# pic24rgbdin-01.net
KiCad netlist of a schematic drawn in EAGLE
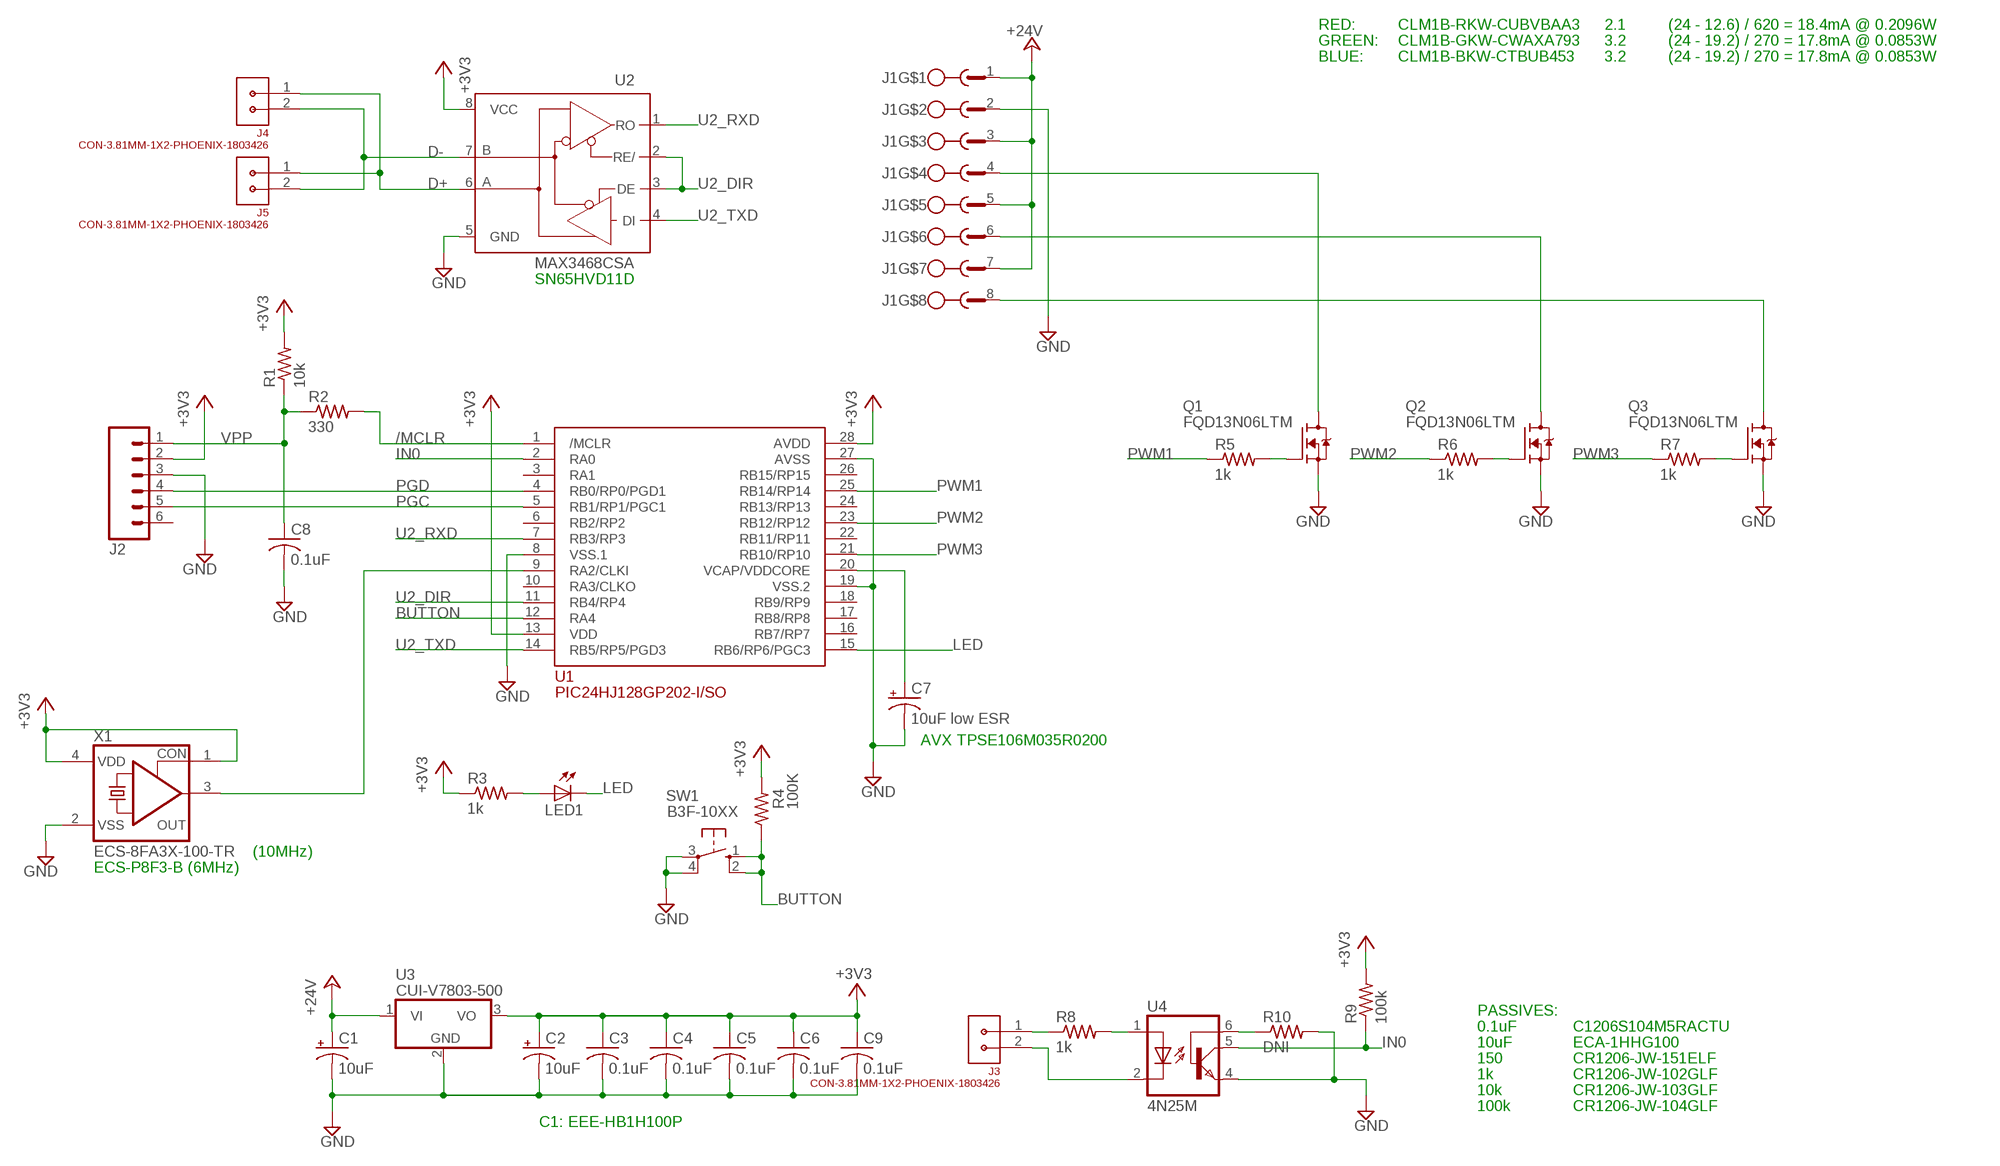
[diagram p0: schematic, sheet 1]

(export (version "E")
  (design (tool "Eeschema 10.0.6"))
  (components
    (comp (ref "C1")
      (value "10uF")
      (footprint "eagle-import:PANASONIC_D")
      (libsource (lib "eagle-import") (part "CPOL-USD"))
    )
    (comp (ref "C2")
      (value "10uF")
      (footprint "eagle-import:PANASONIC_D")
      (libsource (lib "eagle-import") (part "CPOL-USD"))
    )
    (comp (ref "C3")
      (value "0.1uF")
      (footprint "eagle-import:C1206")
      (libsource (lib "eagle-import") (part "C-USC1206"))
    )
    (comp (ref "C4")
      (value "0.1uF")
      (footprint "eagle-import:C1206")
      (libsource (lib "eagle-import") (part "C-USC1206"))
    )
    (comp (ref "C5")
      (value "0.1uF")
      (footprint "eagle-import:C1206")
      (libsource (lib "eagle-import") (part "C-USC1206"))
    )
    (comp (ref "C6")
      (value "0.1uF")
      (footprint "eagle-import:C1206")
      (libsource (lib "eagle-import") (part "C-USC1206"))
    )
    (comp (ref "C7")
      (value "10uF low ESR")
      (footprint "eagle-import:D_7343-31R")
      (libsource (lib "eagle-import") (part "CPOL-USD/7343-31R"))
    )
    (comp (ref "C8")
      (value "0.1uF")
      (footprint "eagle-import:C1206")
      (libsource (lib "eagle-import") (part "C-USC1206"))
    )
    (comp (ref "C9")
      (value "0.1uF")
      (footprint "eagle-import:C1206")
      (libsource (lib "eagle-import") (part "C-USC1206"))
    )
    (comp (ref "J1")
      (value "CON-3.81MM-1X8-PHOENIX-HEADER-1803484")
      (footprint "eagle-import:CON-PHOENIX-1803484-3.81-1X8")
      (libsource (lib "eagle-import") (part "CON-3.81MM-1X8-PHOENIX-HEADER-1803484"))
    )
    (comp (ref "J2")
      (value "M06SIP")
      (footprint "eagle-import:1X06")
      (libsource (lib "eagle-import") (part "M06SIP"))
    )
    (comp (ref "J3")
      (value "CON-3.81MM-1X2-PHOENIX-1803426")
      (footprint "eagle-import:CON-PHOENIX-1803426-3.81-1X2")
      (libsource (lib "eagle-import") (part "CON-3.81MM-1X2-PHOENIX-1803426"))
    )
    (comp (ref "J4")
      (value "CON-3.81MM-1X2-PHOENIX-1803426")
      (footprint "eagle-import:CON-PHOENIX-1803426-3.81-1X2")
      (libsource (lib "eagle-import") (part "CON-3.81MM-1X2-PHOENIX-1803426"))
    )
    (comp (ref "J5")
      (value "CON-3.81MM-1X2-PHOENIX-1803426")
      (footprint "eagle-import:CON-PHOENIX-1803426-3.81-1X2")
      (libsource (lib "eagle-import") (part "CON-3.81MM-1X2-PHOENIX-1803426"))
    )
    (comp (ref "LED1")
      (value "LED3MM")
      (footprint "eagle-import:LED3MM")
      (libsource (lib "eagle-import") (part "LED3MM"))
    )
    (comp (ref "Q1")
      (value "FQD13N06LTM")
      (footprint "eagle-import:TO252-D-PAK-FQD13N06LTM")
      (libsource (lib "eagle-import") (part "FQD13N06L"))
    )
    (comp (ref "Q2")
      (value "FQD13N06LTM")
      (footprint "eagle-import:TO252-D-PAK-FQD13N06LTM")
      (libsource (lib "eagle-import") (part "FQD13N06L"))
    )
    (comp (ref "Q3")
      (value "FQD13N06LTM")
      (footprint "eagle-import:TO252-D-PAK-FQD13N06LTM")
      (libsource (lib "eagle-import") (part "FQD13N06L"))
    )
    (comp (ref "R1")
      (value "10k")
      (footprint "eagle-import:R1206")
      (libsource (lib "eagle-import") (part "R-US_R1206"))
    )
    (comp (ref "R2")
      (value "330")
      (footprint "eagle-import:R1206")
      (libsource (lib "eagle-import") (part "R-US_R1206"))
    )
    (comp (ref "R3")
      (value "1k")
      (footprint "eagle-import:R1206")
      (libsource (lib "eagle-import") (part "R-US_R1206"))
    )
    (comp (ref "R4")
      (value "100K")
      (footprint "eagle-import:M1206")
      (libsource (lib "eagle-import") (part "R-US_M1206"))
    )
    (comp (ref "R5")
      (value "1k")
      (footprint "eagle-import:R1206")
      (libsource (lib "eagle-import") (part "R-US_R1206"))
    )
    (comp (ref "R6")
      (value "1k")
      (footprint "eagle-import:R1206")
      (libsource (lib "eagle-import") (part "R-US_R1206"))
    )
    (comp (ref "R7")
      (value "1k")
      (footprint "eagle-import:R1206")
      (libsource (lib "eagle-import") (part "R-US_R1206"))
    )
    (comp (ref "R8")
      (value "1k")
      (footprint "eagle-import:R1206")
      (libsource (lib "eagle-import") (part "R-US_R1206"))
    )
    (comp (ref "R9")
      (value "100k")
      (footprint "eagle-import:R1206")
      (libsource (lib "eagle-import") (part "R-US_R1206"))
    )
    (comp (ref "R10")
      (value "DNI")
      (footprint "eagle-import:R1206")
      (libsource (lib "eagle-import") (part "R-US_R1206"))
    )
    (comp (ref "SW1")
      (value "B3F-10XX")
      (footprint "eagle-import:B3F-10XX")
      (libsource (lib "eagle-import") (part "10-XX"))
    )
    (comp (ref "U1")
      (value "PIC24HJ128GP202-I/SO")
      (footprint "eagle-import:SO28W")
      (libsource (lib "eagle-import") (part "PIC24HJ128GP202-I/SO"))
    )
    (comp (ref "U2")
      (value "MAX3468CSA")
      (footprint "eagle-import:SO08")
      (fields (field (name "MPN") "MAX3468CSA+"))
      (libsource (lib "eagle-import") (part "MAX34SA68C"))
    )
    (comp (ref "U3")
      (value "CUI-V7803-500")
      (footprint "eagle-import:CUI-78XX-500")
      (libsource (lib "eagle-import") (part "CUI-V7803-500"))
    )
    (comp (ref "U4")
      (value "4N25M")
      (footprint "eagle-import:DIL06")
      (fields (field (name "MPN") "4N25-M"))
      (libsource (lib "eagle-import") (part "4N?M25"))
    )
    (comp (ref "X1")
      (value "ECS-8FA3X-100-TR")
      (footprint "eagle-import:1100S")
      (libsource (lib "eagle-import") (part "CRYSTAL_RES-1100S"))
    )
  )
  (nets
    (net (code "1") (name "+3V3") (class "Default")
      (node (ref "C2") (pin "+") (pinfunction "+_+") (pintype "passive"))
      (node (ref "C3") (pin "1") (pinfunction "1_1") (pintype "passive"))
      (node (ref "C4") (pin "1") (pinfunction "1_1") (pintype "passive"))
      (node (ref "C5") (pin "1") (pinfunction "1_1") (pintype "passive"))
      (node (ref "C6") (pin "1") (pinfunction "1_1") (pintype "passive"))
      (node (ref "C9") (pin "1") (pinfunction "1_1") (pintype "passive"))
      (node (ref "J2") (pin "2") (pinfunction "2_2") (pintype "passive"))
      (node (ref "R1") (pin "2") (pinfunction "2_2") (pintype "passive"))
      (node (ref "R3") (pin "1") (pinfunction "1_1") (pintype "passive"))
      (node (ref "R4") (pin "2") (pinfunction "2_2") (pintype "passive"))
      (node (ref "R9") (pin "2") (pinfunction "2_2") (pintype "passive"))
      (node (ref "U1") (pin "13") (pinfunction "VDD_13") (pintype "bidirectional"))
      (node (ref "U1") (pin "28") (pinfunction "AVDD_28") (pintype "bidirectional"))
      (node (ref "U2") (pin "8") (pinfunction "VCC_8") (pintype "power_in"))
      (node (ref "U3") (pin "3") (pinfunction "VO_3") (pintype "passive"))
      (node (ref "X1") (pin "1") (pinfunction "CON_1") (pintype "input"))
      (node (ref "X1") (pin "4") (pinfunction "VDD_4") (pintype "power_in"))
    )
    (net (code "2") (name "+24V") (class "Default")
      (node (ref "C1") (pin "+") (pinfunction "+_+") (pintype "passive"))
      (node (ref "J1") (pin "1") (pinfunction "1_1") (pintype "passive"))
      (node (ref "J1") (pin "3") (pinfunction "1_3") (pintype "passive"))
      (node (ref "J1") (pin "5") (pinfunction "1_5") (pintype "passive"))
      (node (ref "J1") (pin "7") (pinfunction "1_7") (pintype "passive"))
      (node (ref "U3") (pin "1") (pinfunction "VI_1") (pintype "input"))
    )
    (net (code "3") (name "/BUTTON") (class "Default")
      (node (ref "R4") (pin "1") (pinfunction "1_1") (pintype "passive"))
      (node (ref "SW1") (pin "1") (pinfunction "S_1") (pintype "passive"))
      (node (ref "SW1") (pin "2") (pinfunction "S1_2") (pintype "passive"))
      (node (ref "U1") (pin "12") (pinfunction "RA4_12") (pintype "bidirectional"))
    )
    (net (code "4") (name "/D+") (class "Default")
      (node (ref "J4") (pin "1") (pinfunction "1_1") (pintype "bidirectional"))
      (node (ref "J5") (pin "1") (pinfunction "1_1") (pintype "bidirectional"))
      (node (ref "U2") (pin "6") (pinfunction "A_6") (pintype "passive"))
    )
    (net (code "5") (name "/D-") (class "Default")
      (node (ref "J4") (pin "2") (pinfunction "2_2") (pintype "bidirectional"))
      (node (ref "J5") (pin "2") (pinfunction "2_2") (pintype "bidirectional"))
      (node (ref "U2") (pin "7") (pinfunction "B_7") (pintype "passive"))
    )
    (net (code "6") (name "/IN0") (class "Default")
      (node (ref "R9") (pin "1") (pinfunction "1_1") (pintype "passive"))
      (node (ref "U1") (pin "2") (pinfunction "RA0_2") (pintype "bidirectional"))
      (node (ref "U4") (pin "5") (pinfunction "COL_5") (pintype "passive"))
    )
    (net (code "7") (name "/LED") (class "Default")
      (node (ref "LED1") (pin "K") (pinfunction "C_K") (pintype "passive"))
      (node (ref "U1") (pin "15") (pinfunction "RB6/RP6/PGC3_15") (pintype "bidirectional"))
    )
    (net (code "8") (name "/PGC") (class "Default")
      (node (ref "J2") (pin "5") (pinfunction "5_5") (pintype "passive"))
      (node (ref "U1") (pin "5") (pinfunction "RB1/RP1/PGC1_5") (pintype "bidirectional"))
    )
    (net (code "9") (name "/PGD") (class "Default")
      (node (ref "J2") (pin "4") (pinfunction "4_4") (pintype "passive"))
      (node (ref "U1") (pin "4") (pinfunction "RB0/RP0/PGD1_4") (pintype "bidirectional"))
    )
    (net (code "10") (name "/PWM1") (class "Default")
      (node (ref "R5") (pin "1") (pinfunction "1_1") (pintype "passive"))
      (node (ref "U1") (pin "25") (pinfunction "RB14/RP14_25") (pintype "bidirectional"))
    )
    (net (code "11") (name "/PWM2") (class "Default")
      (node (ref "R6") (pin "1") (pinfunction "1_1") (pintype "passive"))
      (node (ref "U1") (pin "23") (pinfunction "RB12/RP12_23") (pintype "bidirectional"))
    )
    (net (code "12") (name "/PWM3") (class "Default")
      (node (ref "R7") (pin "1") (pinfunction "1_1") (pintype "passive"))
      (node (ref "U1") (pin "21") (pinfunction "RB10/RP10_21") (pintype "bidirectional"))
    )
    (net (code "13") (name "/U2_DIR") (class "Default")
      (node (ref "U1") (pin "11") (pinfunction "RB4/RP4_11") (pintype "bidirectional"))
      (node (ref "U2") (pin "2") (pinfunction "RE/_2") (pintype "input"))
      (node (ref "U2") (pin "3") (pinfunction "DE_3") (pintype "input"))
    )
    (net (code "14") (name "/U2_RXD") (class "Default")
      (node (ref "U1") (pin "7") (pinfunction "RB3/RP3_7") (pintype "bidirectional"))
      (node (ref "U2") (pin "1") (pinfunction "RO_1") (pintype "output"))
    )
    (net (code "15") (name "/U2_TXD") (class "Default")
      (node (ref "U1") (pin "14") (pinfunction "RB5/RP5/PGD3_14") (pintype "bidirectional"))
      (node (ref "U2") (pin "4") (pinfunction "DI_4") (pintype "input"))
    )
    (net (code "16") (name "/VPP") (class "Default")
      (node (ref "C8") (pin "1") (pinfunction "1_1") (pintype "passive"))
      (node (ref "J2") (pin "1") (pinfunction "1_1") (pintype "passive"))
      (node (ref "R1") (pin "1") (pinfunction "1_1") (pintype "passive"))
      (node (ref "R2") (pin "1") (pinfunction "1_1") (pintype "passive"))
    )
    (net (code "17") (name "/{slash}MCLR") (class "Default")
      (node (ref "R2") (pin "2") (pinfunction "2_2") (pintype "passive"))
      (node (ref "U1") (pin "1") (pinfunction "/MCLR_1") (pintype "bidirectional"))
    )
    (net (code "18") (name "GND") (class "Default")
      (node (ref "C1") (pin "-") (pinfunction "-_-") (pintype "passive"))
      (node (ref "C2") (pin "-") (pinfunction "-_-") (pintype "passive"))
      (node (ref "C3") (pin "2") (pinfunction "2_2") (pintype "passive"))
      (node (ref "C4") (pin "2") (pinfunction "2_2") (pintype "passive"))
      (node (ref "C5") (pin "2") (pinfunction "2_2") (pintype "passive"))
      (node (ref "C6") (pin "2") (pinfunction "2_2") (pintype "passive"))
      (node (ref "C7") (pin "-") (pinfunction "-_-") (pintype "passive"))
      (node (ref "C8") (pin "2") (pinfunction "2_2") (pintype "passive"))
      (node (ref "C9") (pin "2") (pinfunction "2_2") (pintype "passive"))
      (node (ref "J1") (pin "2") (pinfunction "1_2") (pintype "passive"))
      (node (ref "J2") (pin "3") (pinfunction "3_3") (pintype "passive"))
      (node (ref "Q1") (pin "P$3") (pinfunction "S_P$3") (pintype "passive"))
      (node (ref "Q2") (pin "P$3") (pinfunction "S_P$3") (pintype "passive"))
      (node (ref "Q3") (pin "P$3") (pinfunction "S_P$3") (pintype "passive"))
      (node (ref "R10") (pin "2") (pinfunction "2_2") (pintype "passive"))
      (node (ref "SW1") (pin "3") (pinfunction "P_3") (pintype "passive"))
      (node (ref "SW1") (pin "4") (pinfunction "P1_4") (pintype "passive"))
      (node (ref "U1") (pin "19") (pinfunction "VSS.2_19") (pintype "bidirectional"))
      (node (ref "U1") (pin "27") (pinfunction "AVSS_27") (pintype "bidirectional"))
      (node (ref "U1") (pin "8") (pinfunction "VSS.1_8") (pintype "bidirectional"))
      (node (ref "U2") (pin "5") (pinfunction "GND_5") (pintype "power_in"))
      (node (ref "U3") (pin "2") (pinfunction "GND_2") (pintype "passive"))
      (node (ref "U4") (pin "4") (pinfunction "EMI_4") (pintype "passive"))
      (node (ref "X1") (pin "2") (pinfunction "VSS_2") (pintype "power_in"))
    )
    (net (code "19") (name "Net-(J1D-1)") (class "Default")
      (node (ref "J1") (pin "4") (pinfunction "1_4") (pintype "passive"))
      (node (ref "Q1") (pin "P$4") (pinfunction "D_P$4") (pintype "passive"))
    )
    (net (code "20") (name "Net-(J1F-1)") (class "Default")
      (node (ref "J1") (pin "6") (pinfunction "1_6") (pintype "passive"))
      (node (ref "Q2") (pin "P$4") (pinfunction "D_P$4") (pintype "passive"))
    )
    (net (code "21") (name "Net-(J1H-1)") (class "Default")
      (node (ref "J1") (pin "8") (pinfunction "1_8") (pintype "passive"))
      (node (ref "Q3") (pin "P$4") (pinfunction "D_P$4") (pintype "passive"))
    )
    (net (code "22") (name "Net-(J3-Pad1)") (class "Default")
      (node (ref "J3") (pin "1") (pinfunction "1_1") (pintype "bidirectional"))
      (node (ref "R8") (pin "1") (pinfunction "1_1") (pintype "passive"))
    )
    (net (code "23") (name "Net-(LED1-PadA)") (class "Default")
      (node (ref "LED1") (pin "A") (pinfunction "A_A") (pintype "passive"))
      (node (ref "R3") (pin "2") (pinfunction "2_2") (pintype "passive"))
    )
    (net (code "24") (name "Net-(Q1-G)") (class "Default")
      (node (ref "Q1") (pin "P$1") (pinfunction "G_P$1") (pintype "passive"))
      (node (ref "R5") (pin "2") (pinfunction "2_2") (pintype "passive"))
    )
    (net (code "25") (name "Net-(Q2-G)") (class "Default")
      (node (ref "Q2") (pin "P$1") (pinfunction "G_P$1") (pintype "passive"))
      (node (ref "R6") (pin "2") (pinfunction "2_2") (pintype "passive"))
    )
    (net (code "26") (name "Net-(Q3-G)") (class "Default")
      (node (ref "Q3") (pin "P$1") (pinfunction "G_P$1") (pintype "passive"))
      (node (ref "R7") (pin "2") (pinfunction "2_2") (pintype "passive"))
    )
    (net (code "27") (name "Net-(U1-RA2{slash}CLKI)") (class "Default")
      (node (ref "U1") (pin "9") (pinfunction "RA2/CLKI_9") (pintype "bidirectional"))
      (node (ref "X1") (pin "3") (pinfunction "OUT_3") (pintype "output"))
    )
    (net (code "28") (name "Net-(U1-VCAP{slash}VDDCORE)") (class "Default")
      (node (ref "C7") (pin "+") (pinfunction "+_+") (pintype "passive"))
      (node (ref "U1") (pin "20") (pinfunction "VCAP/VDDCORE_20") (pintype "bidirectional"))
    )
    (net (code "29") (name "Net-(U4-A)") (class "Default")
      (node (ref "R8") (pin "2") (pinfunction "2_2") (pintype "passive"))
      (node (ref "U4") (pin "1") (pinfunction "A_1") (pintype "passive"))
    )
    (net (code "30") (name "Net-(U4-BAS)") (class "Default")
      (node (ref "R10") (pin "1") (pinfunction "1_1") (pintype "passive"))
      (node (ref "U4") (pin "6") (pinfunction "BAS_6") (pintype "passive"))
    )
    (net (code "31") (name "Net-(U4-C)") (class "Default")
      (node (ref "J3") (pin "2") (pinfunction "2_2") (pintype "bidirectional"))
      (node (ref "U4") (pin "2") (pinfunction "C_2") (pintype "passive"))
    )
    (net (code "32") (name "unconnected-(J2-Pad6)") (class "Default")
      (node (ref "J2") (pin "6") (pinfunction "6_6") (pintype "passive"))
    )
    (net (code "33") (name "unconnected-(U1-RA1-Pad3)") (class "Default")
      (node (ref "U1") (pin "3") (pinfunction "RA1_3") (pintype "bidirectional"))
    )
    (net (code "34") (name "unconnected-(U1-RA3{slash}CLKO-Pad10)") (class "Default")
      (node (ref "U1") (pin "10") (pinfunction "RA3/CLKO_10") (pintype "bidirectional"))
    )
    (net (code "35") (name "unconnected-(U1-RB2{slash}RP2-Pad6)") (class "Default")
      (node (ref "U1") (pin "6") (pinfunction "RB2/RP2_6") (pintype "bidirectional"))
    )
    (net (code "36") (name "unconnected-(U1-RB7{slash}RP7-Pad16)") (class "Default")
      (node (ref "U1") (pin "16") (pinfunction "RB7/RP7_16") (pintype "bidirectional"))
    )
    (net (code "37") (name "unconnected-(U1-RB8{slash}RP8-Pad17)") (class "Default")
      (node (ref "U1") (pin "17") (pinfunction "RB8/RP8_17") (pintype "bidirectional"))
    )
    (net (code "38") (name "unconnected-(U1-RB9{slash}RP9-Pad18)") (class "Default")
      (node (ref "U1") (pin "18") (pinfunction "RB9/RP9_18") (pintype "bidirectional"))
    )
    (net (code "39") (name "unconnected-(U1-RB11{slash}RP11-Pad22)") (class "Default")
      (node (ref "U1") (pin "22") (pinfunction "RB11/RP11_22") (pintype "bidirectional"))
    )
    (net (code "40") (name "unconnected-(U1-RB13{slash}RP13-Pad24)") (class "Default")
      (node (ref "U1") (pin "24") (pinfunction "RB13/RP13_24") (pintype "bidirectional"))
    )
    (net (code "41") (name "unconnected-(U1-RB15{slash}RP15-Pad26)") (class "Default")
      (node (ref "U1") (pin "26") (pinfunction "RB15/RP15_26") (pintype "bidirectional"))
    )
  )
)
